# P07_Flash.net
KiCad netlist of a schematic drawn in Altium Designer
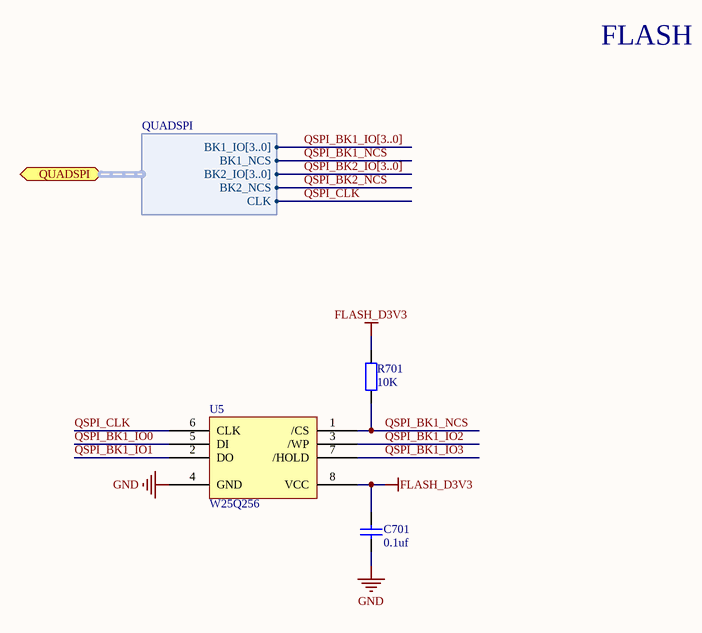
[diagram p0: P07.Flash.SchDoc]

(export (version "E")
  (design (tool "Eeschema 10.0.6"))
  (components
    (comp (ref "C701")
      (value "0.1uf")
      (footprint "C0603")
      (fields (field (name "Comment") "Cap"))
      (libsource (lib "carrot_lib") (part "Cap"))
    )
    (comp (ref "R701")
      (value "10K")
      (footprint "R0603")
      (description "电阻")
      (fields (field (name "Comment") "Res"))
      (libsource (lib "carrot_lib") (part "Res"))
    )
    (comp (ref "U5")
      (value "W25Q256")
      (footprint "W25Q256-WSON8-8X6")
      (description "256M-BIT SERIAL FLASH MEMORY WITH DUAL, QUAD SPI")
      (libsource (lib "carrot_lib") (part "W25Q256"))
    )
  )
  (nets
    (net (code "2") (name "/QSPI_BK1_IO0") (class "Default")
      (node (ref "U5") (pin "5") (pinfunction "DI_5") (pintype "passive"))
    )
    (net (code "3") (name "/QSPI_BK1_IO1") (class "Default")
      (node (ref "U5") (pin "2") (pinfunction "DO_2") (pintype "passive"))
    )
    (net (code "4") (name "/QSPI_BK1_IO2") (class "Default")
      (node (ref "U5") (pin "3") (pinfunction "/WP_3") (pintype "passive"))
    )
    (net (code "5") (name "/QSPI_BK1_IO3") (class "Default")
      (node (ref "U5") (pin "7") (pinfunction "/HOLD_7") (pintype "passive"))
    )
    (net (code "7") (name "/QSPI_BK1_NCS") (class "Default")
      (node (ref "R701") (pin "1") (pinfunction "1_1") (pintype "passive"))
      (node (ref "U5") (pin "1") (pinfunction "/CS_1") (pintype "passive"))
    )
    (net (code "9") (name "/QSPI_CLK") (class "Default")
      (node (ref "U5") (pin "6") (pinfunction "CLK_6") (pintype "passive"))
    )
    (net (code "12") (name "FLASH_D3V3") (class "Default")
      (node (ref "C701") (pin "2") (pinfunction "2_2") (pintype "passive"))
      (node (ref "R701") (pin "2") (pinfunction "2_2") (pintype "passive"))
      (node (ref "U5") (pin "8") (pinfunction "VCC_8") (pintype "passive"))
    )
    (net (code "13") (name "GND") (class "Default")
      (node (ref "C701") (pin "1") (pinfunction "1_1") (pintype "passive"))
      (node (ref "U5") (pin "4") (pinfunction "GND_4") (pintype "passive"))
    )
  )
)
